# Shawn_sNano.net
KiCad netlist of a schematic drawn in EAGLE
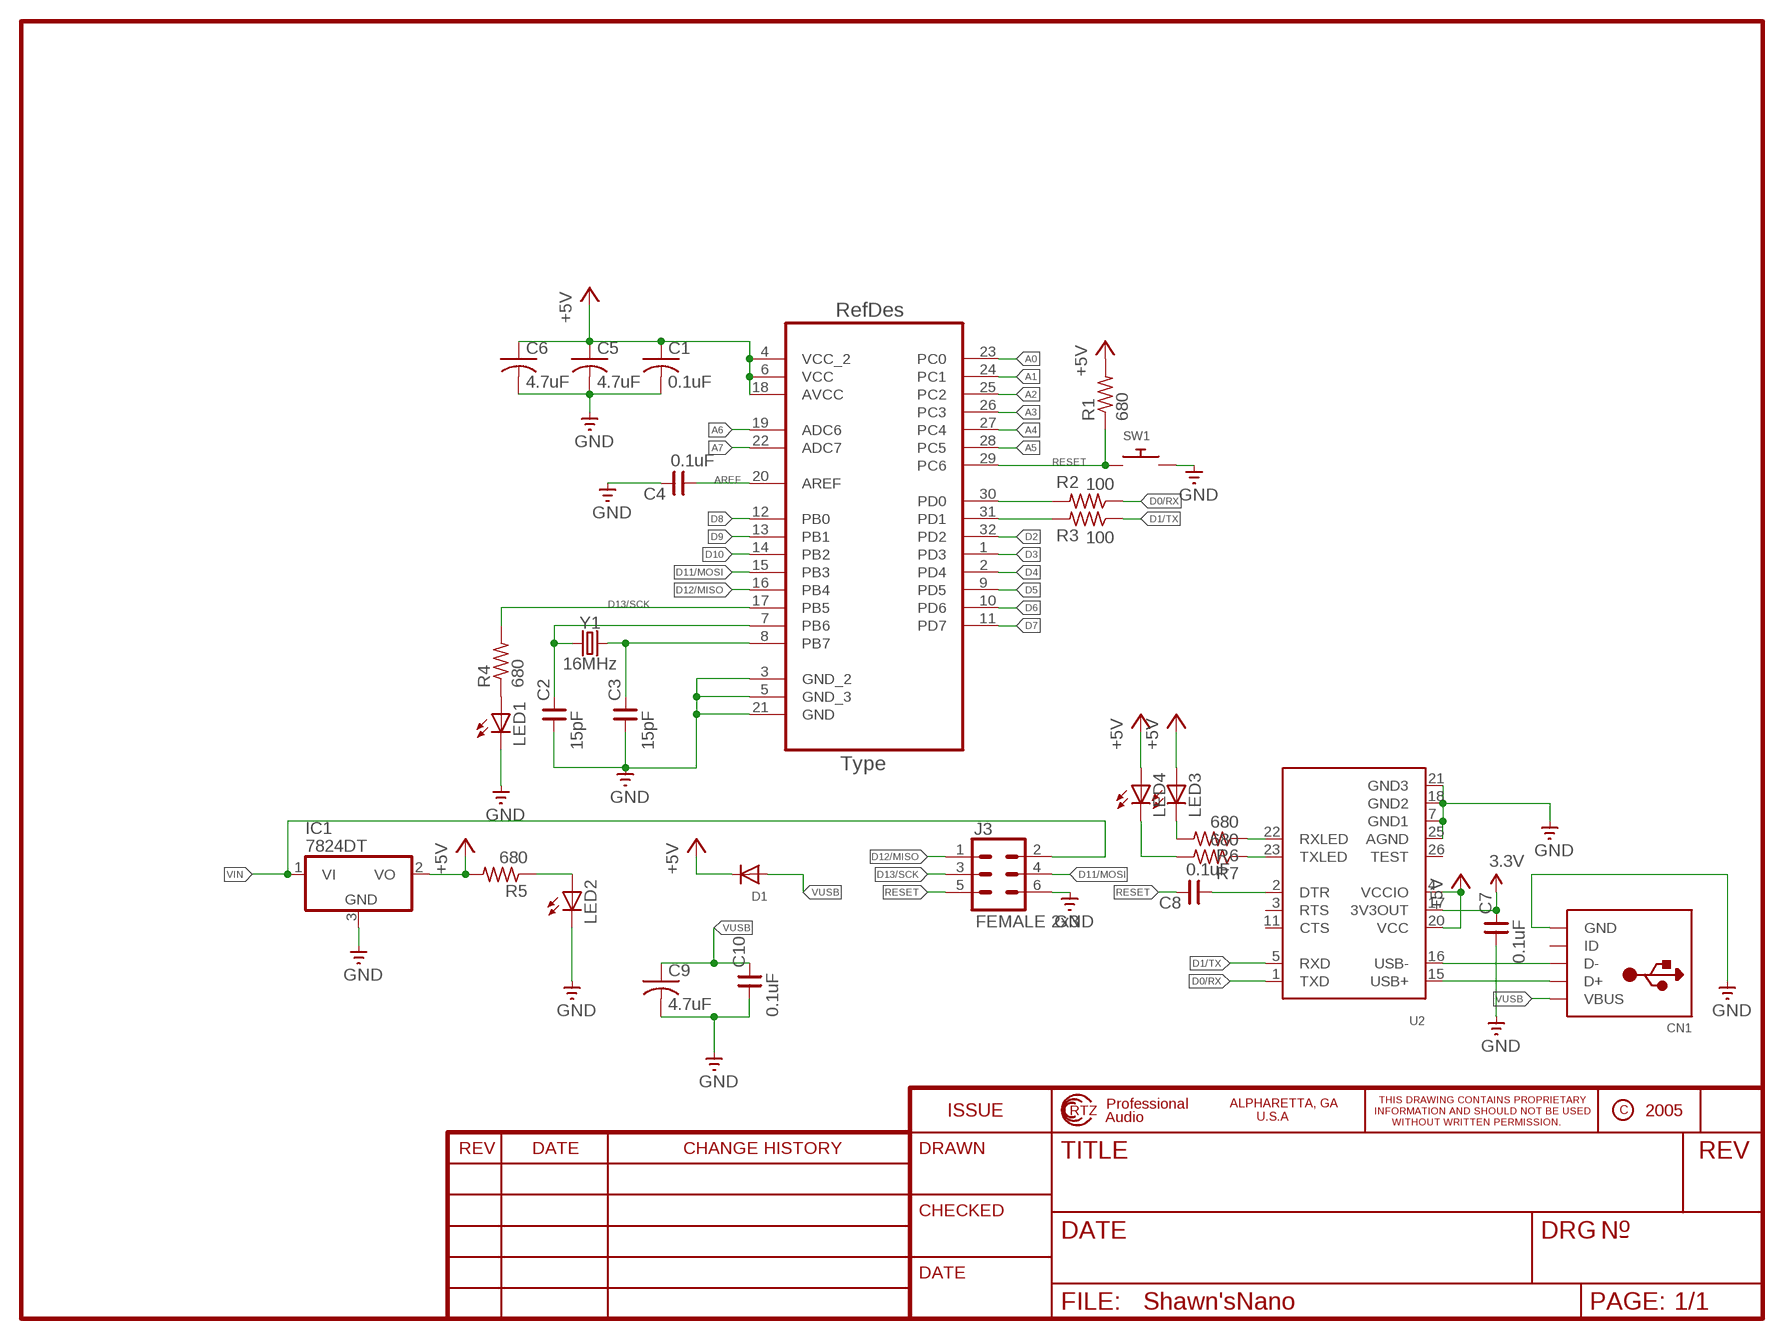
[diagram p0: schematic, sheet 1]

(export (version "E")
  (design (tool "Eeschema 10.0.6"))
  (components
    (comp (ref "C1")
      (value "0.1uF")
      (footprint "eagle-import:C0805")
      (libsource (lib "eagle-import") (part "C-USC0805"))
    )
    (comp (ref "C2")
      (value "15pF")
      (footprint "eagle-import:0805")
      (libsource (lib "eagle-import") (part "CNP-0805"))
    )
    (comp (ref "C3")
      (value "15pF")
      (footprint "eagle-import:0805")
      (libsource (lib "eagle-import") (part "CNP-0805"))
    )
    (comp (ref "C4")
      (value "0.1uF")
      (footprint "eagle-import:0805")
      (libsource (lib "eagle-import") (part "CNP-0805"))
    )
    (comp (ref "C5")
      (value "4.7uF")
      (footprint "eagle-import:C0805")
      (libsource (lib "eagle-import") (part "C-USC0805"))
    )
    (comp (ref "C6")
      (value "4.7uF")
      (footprint "eagle-import:C0805")
      (libsource (lib "eagle-import") (part "C-USC0805"))
    )
    (comp (ref "C7")
      (value "0.1uF")
      (footprint "eagle-import:0805")
      (libsource (lib "eagle-import") (part "CNP-0805"))
    )
    (comp (ref "C8")
      (value "0.1uF")
      (footprint "eagle-import:0805")
      (libsource (lib "eagle-import") (part "CNP-0805"))
    )
    (comp (ref "C9")
      (value "4.7uF")
      (footprint "eagle-import:C0805")
      (libsource (lib "eagle-import") (part "C-USC0805"))
    )
    (comp (ref "C10")
      (value "0.1uF")
      (footprint "eagle-import:0805")
      (libsource (lib "eagle-import") (part "CNP-0805"))
    )
    (comp (ref "CN1")
      (value "USBMINIB")
      (footprint "eagle-import:USB-MINIB")
      (libsource (lib "eagle-import") (part "USBMINIB"))
    )
    (comp (ref "D1")
      (value "DIODESOD-123")
      (footprint "eagle-import:SOD-123")
      (libsource (lib "eagle-import") (part "DIODESOD-123"))
    )
    (comp (ref "IC1")
      (value "7824DT")
      (footprint "eagle-import:TO252")
      (libsource (lib "eagle-import") (part "78DT24"))
    )
    (comp (ref "J3")
      (value "FEMALE 2x3")
      (footprint "eagle-import:2X3")
      (libsource (lib "eagle-import") (part "CONN_03X2FEMALE"))
    )
    (comp (ref "LED1")
      (value "LEDCHIPLED_0805")
      (footprint "eagle-import:CHIPLED_0805")
      (libsource (lib "eagle-import") (part "LEDCHIPLED_0805"))
    )
    (comp (ref "LED2")
      (value "LEDCHIPLED_0805")
      (footprint "eagle-import:CHIPLED_0805")
      (libsource (lib "eagle-import") (part "LEDCHIPLED_0805"))
    )
    (comp (ref "LED3")
      (value "LEDCHIPLED_0805")
      (footprint "eagle-import:CHIPLED_0805")
      (libsource (lib "eagle-import") (part "LEDCHIPLED_0805"))
    )
    (comp (ref "LED4")
      (value "LEDCHIPLED_0805")
      (footprint "eagle-import:CHIPLED_0805")
      (libsource (lib "eagle-import") (part "LEDCHIPLED_0805"))
    )
    (comp (ref "R1")
      (value "680")
      (footprint "eagle-import:R0805")
      (libsource (lib "eagle-import") (part "R-US_R0805"))
    )
    (comp (ref "R2")
      (value "100")
      (footprint "eagle-import:R0805")
      (libsource (lib "eagle-import") (part "R-US_R0805"))
    )
    (comp (ref "R3")
      (value "100")
      (footprint "eagle-import:R0805")
      (libsource (lib "eagle-import") (part "R-US_R0805"))
    )
    (comp (ref "R4")
      (value "680")
      (footprint "eagle-import:R0805")
      (libsource (lib "eagle-import") (part "R-US_R0805"))
    )
    (comp (ref "R5")
      (value "680")
      (footprint "eagle-import:R0805")
      (libsource (lib "eagle-import") (part "R-US_R0805"))
    )
    (comp (ref "R6")
      (value "680")
      (footprint "eagle-import:R0805")
      (libsource (lib "eagle-import") (part "R-US_R0805"))
    )
    (comp (ref "R7")
      (value "680")
      (footprint "eagle-import:R0805")
      (libsource (lib "eagle-import") (part "R-US_R0805"))
    )
    (comp (ref "SW1")
      (value "SWITCH_PUSHBUTTONEVQ-PE")
      (footprint "eagle-import:TACT_PANA-EVQ")
      (libsource (lib "eagle-import") (part "SWITCH_PUSHBUTTONEVQ-PE"))
    )
    (comp (ref "U1")
      (value "ATMEGA328P-AU")
      (footprint "eagle-import:QFP80P900X900X120-32N")
      (libsource (lib "eagle-import") (part "ATMEGA328P-AU"))
    )
    (comp (ref "U2")
      (value "FT232RLSSOP28")
      (footprint "eagle-import:SSOP28DB")
      (libsource (lib "eagle-import") (part "FT232RLSSOP28"))
    )
    (comp (ref "Y1")
      (value "16MHz")
      (footprint "eagle-import:HC49US")
      (libsource (lib "eagle-import") (part "CRYSTAL-16MHZPTH-HC49US"))
    )
  )
  (nets
    (net (code "1") (name "+5V") (class "Default")
      (node (ref "C1") (pin "1") (pinfunction "1_1") (pintype "passive"))
      (node (ref "C5") (pin "1") (pinfunction "1_1") (pintype "passive"))
      (node (ref "C6") (pin "1") (pinfunction "1_1") (pintype "passive"))
      (node (ref "D1") (pin "C") (pinfunction "C_C") (pintype "passive"))
      (node (ref "IC1") (pin "2") (pinfunction "VO_2") (pintype "passive"))
      (node (ref "LED3") (pin "A") (pinfunction "A_A") (pintype "passive"))
      (node (ref "LED4") (pin "A") (pinfunction "A_A") (pintype "passive"))
      (node (ref "R1") (pin "2") (pinfunction "2_2") (pintype "passive"))
      (node (ref "R5") (pin "2") (pinfunction "2_2") (pintype "passive"))
      (node (ref "U1") (pin "18") (pinfunction "AVCC_18") (pintype "power_in"))
      (node (ref "U1") (pin "4") (pinfunction "VCC_2_4") (pintype "power_in"))
      (node (ref "U1") (pin "6") (pinfunction "VCC_6") (pintype "power_in"))
      (node (ref "U2") (pin "20") (pinfunction "VCC_20") (pintype "power_in"))
      (node (ref "U2") (pin "4") (pinfunction "VCCIO_4") (pintype "power_in"))
    )
    (net (code "2") (name "/AREF") (class "Default")
      (node (ref "C4") (pin "1") (pinfunction "1_1") (pintype "passive"))
      (node (ref "U1") (pin "20") (pinfunction "AREF_20") (pintype "input"))
    )
    (net (code "3") (name "3.3V") (class "Default")
      (node (ref "C7") (pin "2") (pinfunction "2_2") (pintype "passive"))
      (node (ref "U2") (pin "17") (pinfunction "3V3OUT_17") (pintype "power_in"))
    )
    (net (code "4") (name "A0") (class "Default")
      (node (ref "U1") (pin "23") (pinfunction "PC0_23") (pintype "bidirectional"))
    )
    (net (code "5") (name "A1") (class "Default")
      (node (ref "U1") (pin "24") (pinfunction "PC1_24") (pintype "bidirectional"))
    )
    (net (code "6") (name "A2") (class "Default")
      (node (ref "U1") (pin "25") (pinfunction "PC2_25") (pintype "bidirectional"))
    )
    (net (code "7") (name "A3") (class "Default")
      (node (ref "U1") (pin "26") (pinfunction "PC3_26") (pintype "bidirectional"))
    )
    (net (code "8") (name "A4") (class "Default")
      (node (ref "U1") (pin "27") (pinfunction "PC4_27") (pintype "bidirectional"))
    )
    (net (code "9") (name "A5") (class "Default")
      (node (ref "U1") (pin "28") (pinfunction "PC5_28") (pintype "bidirectional"))
    )
    (net (code "10") (name "A6") (class "Default")
      (node (ref "U1") (pin "19") (pinfunction "ADC6_19") (pintype "input"))
    )
    (net (code "11") (name "A7") (class "Default")
      (node (ref "U1") (pin "22") (pinfunction "ADC7_22") (pintype "input"))
    )
    (net (code "12") (name "D0{slash}RX") (class "Default")
      (node (ref "R2") (pin "1") (pinfunction "1_1") (pintype "passive"))
      (node (ref "U2") (pin "1") (pinfunction "TXD_1") (pintype "output"))
    )
    (net (code "13") (name "D1{slash}TX") (class "Default")
      (node (ref "R3") (pin "1") (pinfunction "1_1") (pintype "passive"))
      (node (ref "U2") (pin "5") (pinfunction "RXD_5") (pintype "input"))
    )
    (net (code "14") (name "D2") (class "Default")
      (node (ref "U1") (pin "32") (pinfunction "PD2_32") (pintype "bidirectional"))
    )
    (net (code "15") (name "D3") (class "Default")
      (node (ref "U1") (pin "1") (pinfunction "PD3_1") (pintype "bidirectional"))
    )
    (net (code "16") (name "D4") (class "Default")
      (node (ref "U1") (pin "2") (pinfunction "PD4_2") (pintype "bidirectional"))
    )
    (net (code "17") (name "D5") (class "Default")
      (node (ref "U1") (pin "9") (pinfunction "PD5_9") (pintype "bidirectional"))
    )
    (net (code "18") (name "D6") (class "Default")
      (node (ref "U1") (pin "10") (pinfunction "PD6_10") (pintype "bidirectional"))
    )
    (net (code "19") (name "D7") (class "Default")
      (node (ref "U1") (pin "11") (pinfunction "PD7_11") (pintype "bidirectional"))
    )
    (net (code "20") (name "D8") (class "Default")
      (node (ref "U1") (pin "12") (pinfunction "PB0_12") (pintype "bidirectional"))
    )
    (net (code "21") (name "D9") (class "Default")
      (node (ref "U1") (pin "13") (pinfunction "PB1_13") (pintype "bidirectional"))
    )
    (net (code "22") (name "D10") (class "Default")
      (node (ref "U1") (pin "14") (pinfunction "PB2_14") (pintype "bidirectional"))
    )
    (net (code "23") (name "D11{slash}MOSI") (class "Default")
      (node (ref "J3") (pin "4") (pinfunction "4_4") (pintype "bidirectional"))
      (node (ref "U1") (pin "15") (pinfunction "PB3_15") (pintype "bidirectional"))
    )
    (net (code "24") (name "D12{slash}MISO") (class "Default")
      (node (ref "J3") (pin "1") (pinfunction "1_1") (pintype "bidirectional"))
      (node (ref "U1") (pin "16") (pinfunction "PB4_16") (pintype "bidirectional"))
    )
    (net (code "25") (name "D13{slash}SCK") (class "Default")
      (node (ref "J3") (pin "3") (pinfunction "3_3") (pintype "bidirectional"))
      (node (ref "R4") (pin "2") (pinfunction "2_2") (pintype "passive"))
      (node (ref "U1") (pin "17") (pinfunction "PB5_17") (pintype "bidirectional"))
    )
    (net (code "26") (name "GND") (class "Default")
      (node (ref "C1") (pin "2") (pinfunction "2_2") (pintype "passive"))
      (node (ref "C10") (pin "1") (pinfunction "1_1") (pintype "passive"))
      (node (ref "C2") (pin "1") (pinfunction "1_1") (pintype "passive"))
      (node (ref "C3") (pin "1") (pinfunction "1_1") (pintype "passive"))
      (node (ref "C4") (pin "2") (pinfunction "2_2") (pintype "passive"))
      (node (ref "C5") (pin "2") (pinfunction "2_2") (pintype "passive"))
      (node (ref "C6") (pin "2") (pinfunction "2_2") (pintype "passive"))
      (node (ref "C7") (pin "1") (pinfunction "1_1") (pintype "passive"))
      (node (ref "C9") (pin "2") (pinfunction "2_2") (pintype "passive"))
      (node (ref "CN1") (pin "GND") (pinfunction "GND_GND") (pintype "power_in"))
      (node (ref "IC1") (pin "3") (pinfunction "GND_3") (pintype "passive"))
      (node (ref "J3") (pin "6") (pinfunction "6_6") (pintype "bidirectional"))
      (node (ref "LED1") (pin "C") (pinfunction "C_C") (pintype "passive"))
      (node (ref "LED2") (pin "C") (pinfunction "C_C") (pintype "passive"))
      (node (ref "SW1") (pin "P$2") (pinfunction "P$2_P$2") (pintype "passive"))
      (node (ref "U1") (pin "21") (pinfunction "GND_21") (pintype "passive"))
      (node (ref "U1") (pin "3") (pinfunction "GND_2_3") (pintype "passive"))
      (node (ref "U1") (pin "5") (pinfunction "GND_3_5") (pintype "passive"))
      (node (ref "U2") (pin "18") (pinfunction "GND2_18") (pintype "power_in"))
      (node (ref "U2") (pin "21") (pinfunction "GND3_21") (pintype "power_in"))
      (node (ref "U2") (pin "25") (pinfunction "AGND_25") (pintype "power_in"))
      (node (ref "U2") (pin "7") (pinfunction "GND1_7") (pintype "power_in"))
    )
    (net (code "27") (name "Net-(LED1-PadA)") (class "Default")
      (node (ref "LED1") (pin "A") (pinfunction "A_A") (pintype "passive"))
      (node (ref "R4") (pin "1") (pinfunction "1_1") (pintype "passive"))
    )
    (net (code "28") (name "Net-(LED2-PadA)") (class "Default")
      (node (ref "LED2") (pin "A") (pinfunction "A_A") (pintype "passive"))
      (node (ref "R5") (pin "1") (pinfunction "1_1") (pintype "passive"))
    )
    (net (code "29") (name "Net-(LED3-PadC)") (class "Default")
      (node (ref "LED3") (pin "C") (pinfunction "C_C") (pintype "passive"))
      (node (ref "R6") (pin "2") (pinfunction "2_2") (pintype "passive"))
    )
    (net (code "30") (name "Net-(LED4-PadC)") (class "Default")
      (node (ref "LED4") (pin "C") (pinfunction "C_C") (pintype "passive"))
      (node (ref "R7") (pin "2") (pinfunction "2_2") (pintype "passive"))
    )
    (net (code "31") (name "Net-(U1-PB6)") (class "Default")
      (node (ref "C2") (pin "2") (pinfunction "2_2") (pintype "passive"))
      (node (ref "U1") (pin "7") (pinfunction "PB6_7") (pintype "bidirectional"))
      (node (ref "Y1") (pin "1") (pinfunction "1_1") (pintype "passive"))
    )
    (net (code "32") (name "Net-(U1-PB7)") (class "Default")
      (node (ref "C3") (pin "2") (pinfunction "2_2") (pintype "passive"))
      (node (ref "U1") (pin "8") (pinfunction "PB7_8") (pintype "bidirectional"))
      (node (ref "Y1") (pin "2") (pinfunction "2_2") (pintype "passive"))
    )
    (net (code "33") (name "Net-(U1-PD0)") (class "Default")
      (node (ref "R2") (pin "2") (pinfunction "2_2") (pintype "passive"))
      (node (ref "U1") (pin "30") (pinfunction "PD0_30") (pintype "bidirectional"))
    )
    (net (code "34") (name "Net-(U1-PD1)") (class "Default")
      (node (ref "R3") (pin "2") (pinfunction "2_2") (pintype "passive"))
      (node (ref "U1") (pin "31") (pinfunction "PD1_31") (pintype "bidirectional"))
    )
    (net (code "35") (name "Net-(U2-DTR)") (class "Default")
      (node (ref "C8") (pin "1") (pinfunction "1_1") (pintype "passive"))
      (node (ref "U2") (pin "2") (pinfunction "DTR_2") (pintype "bidirectional"))
    )
    (net (code "36") (name "Net-(U2-RXLED)") (class "Default")
      (node (ref "R6") (pin "1") (pinfunction "1_1") (pintype "passive"))
      (node (ref "U2") (pin "22") (pinfunction "RXLED_22") (pintype "bidirectional"))
    )
    (net (code "37") (name "Net-(U2-TXLED)") (class "Default")
      (node (ref "R7") (pin "1") (pinfunction "1_1") (pintype "passive"))
      (node (ref "U2") (pin "23") (pinfunction "TXLED_23") (pintype "bidirectional"))
    )
    (net (code "38") (name "Net-(U2-USB+)") (class "Default")
      (node (ref "CN1") (pin "D+") (pinfunction "D+_D+") (pintype "bidirectional"))
      (node (ref "U2") (pin "15") (pinfunction "USB+_15") (pintype "bidirectional"))
    )
    (net (code "39") (name "Net-(U2-USB-)") (class "Default")
      (node (ref "CN1") (pin "D-") (pinfunction "D-_D-") (pintype "bidirectional"))
      (node (ref "U2") (pin "16") (pinfunction "USB-_16") (pintype "bidirectional"))
    )
    (net (code "40") (name "RESET") (class "Default")
      (node (ref "C8") (pin "2") (pinfunction "2_2") (pintype "passive"))
      (node (ref "J3") (pin "5") (pinfunction "5_5") (pintype "bidirectional"))
      (node (ref "R1") (pin "1") (pinfunction "1_1") (pintype "passive"))
      (node (ref "SW1") (pin "P$1") (pinfunction "P$1_P$1") (pintype "passive"))
      (node (ref "U1") (pin "29") (pinfunction "PC6_29") (pintype "bidirectional"))
    )
    (net (code "41") (name "VIN") (class "Default")
      (node (ref "IC1") (pin "1") (pinfunction "VI_1") (pintype "input"))
      (node (ref "J3") (pin "2") (pinfunction "2_2") (pintype "bidirectional"))
    )
    (net (code "42") (name "VUSB") (class "Default")
      (node (ref "C10") (pin "2") (pinfunction "2_2") (pintype "passive"))
      (node (ref "C9") (pin "1") (pinfunction "1_1") (pintype "passive"))
      (node (ref "CN1") (pin "VBUS") (pinfunction "VBUS_VBUS") (pintype "power_in"))
      (node (ref "D1") (pin "A") (pinfunction "A_A") (pintype "passive"))
    )
    (net (code "43") (name "unconnected-(CN1-PadID)") (class "Default")
      (node (ref "CN1") (pin "ID") (pinfunction "ID_ID") (pintype "bidirectional"))
    )
    (net (code "44") (name "unconnected-(U2-CTS-Pad11)") (class "Default")
      (node (ref "U2") (pin "11") (pinfunction "CTS_11") (pintype "bidirectional"))
    )
    (net (code "45") (name "unconnected-(U2-RTS-Pad3)") (class "Default")
      (node (ref "U2") (pin "3") (pinfunction "RTS_3") (pintype "bidirectional"))
    )
    (net (code "46") (name "unconnected-(U2-TEST-Pad26)") (class "Default")
      (node (ref "U2") (pin "26") (pinfunction "TEST_26") (pintype "input"))
    )
  )
)
